# TransmitterSchematic.net
KiCad netlist of a schematic drawn in EAGLE
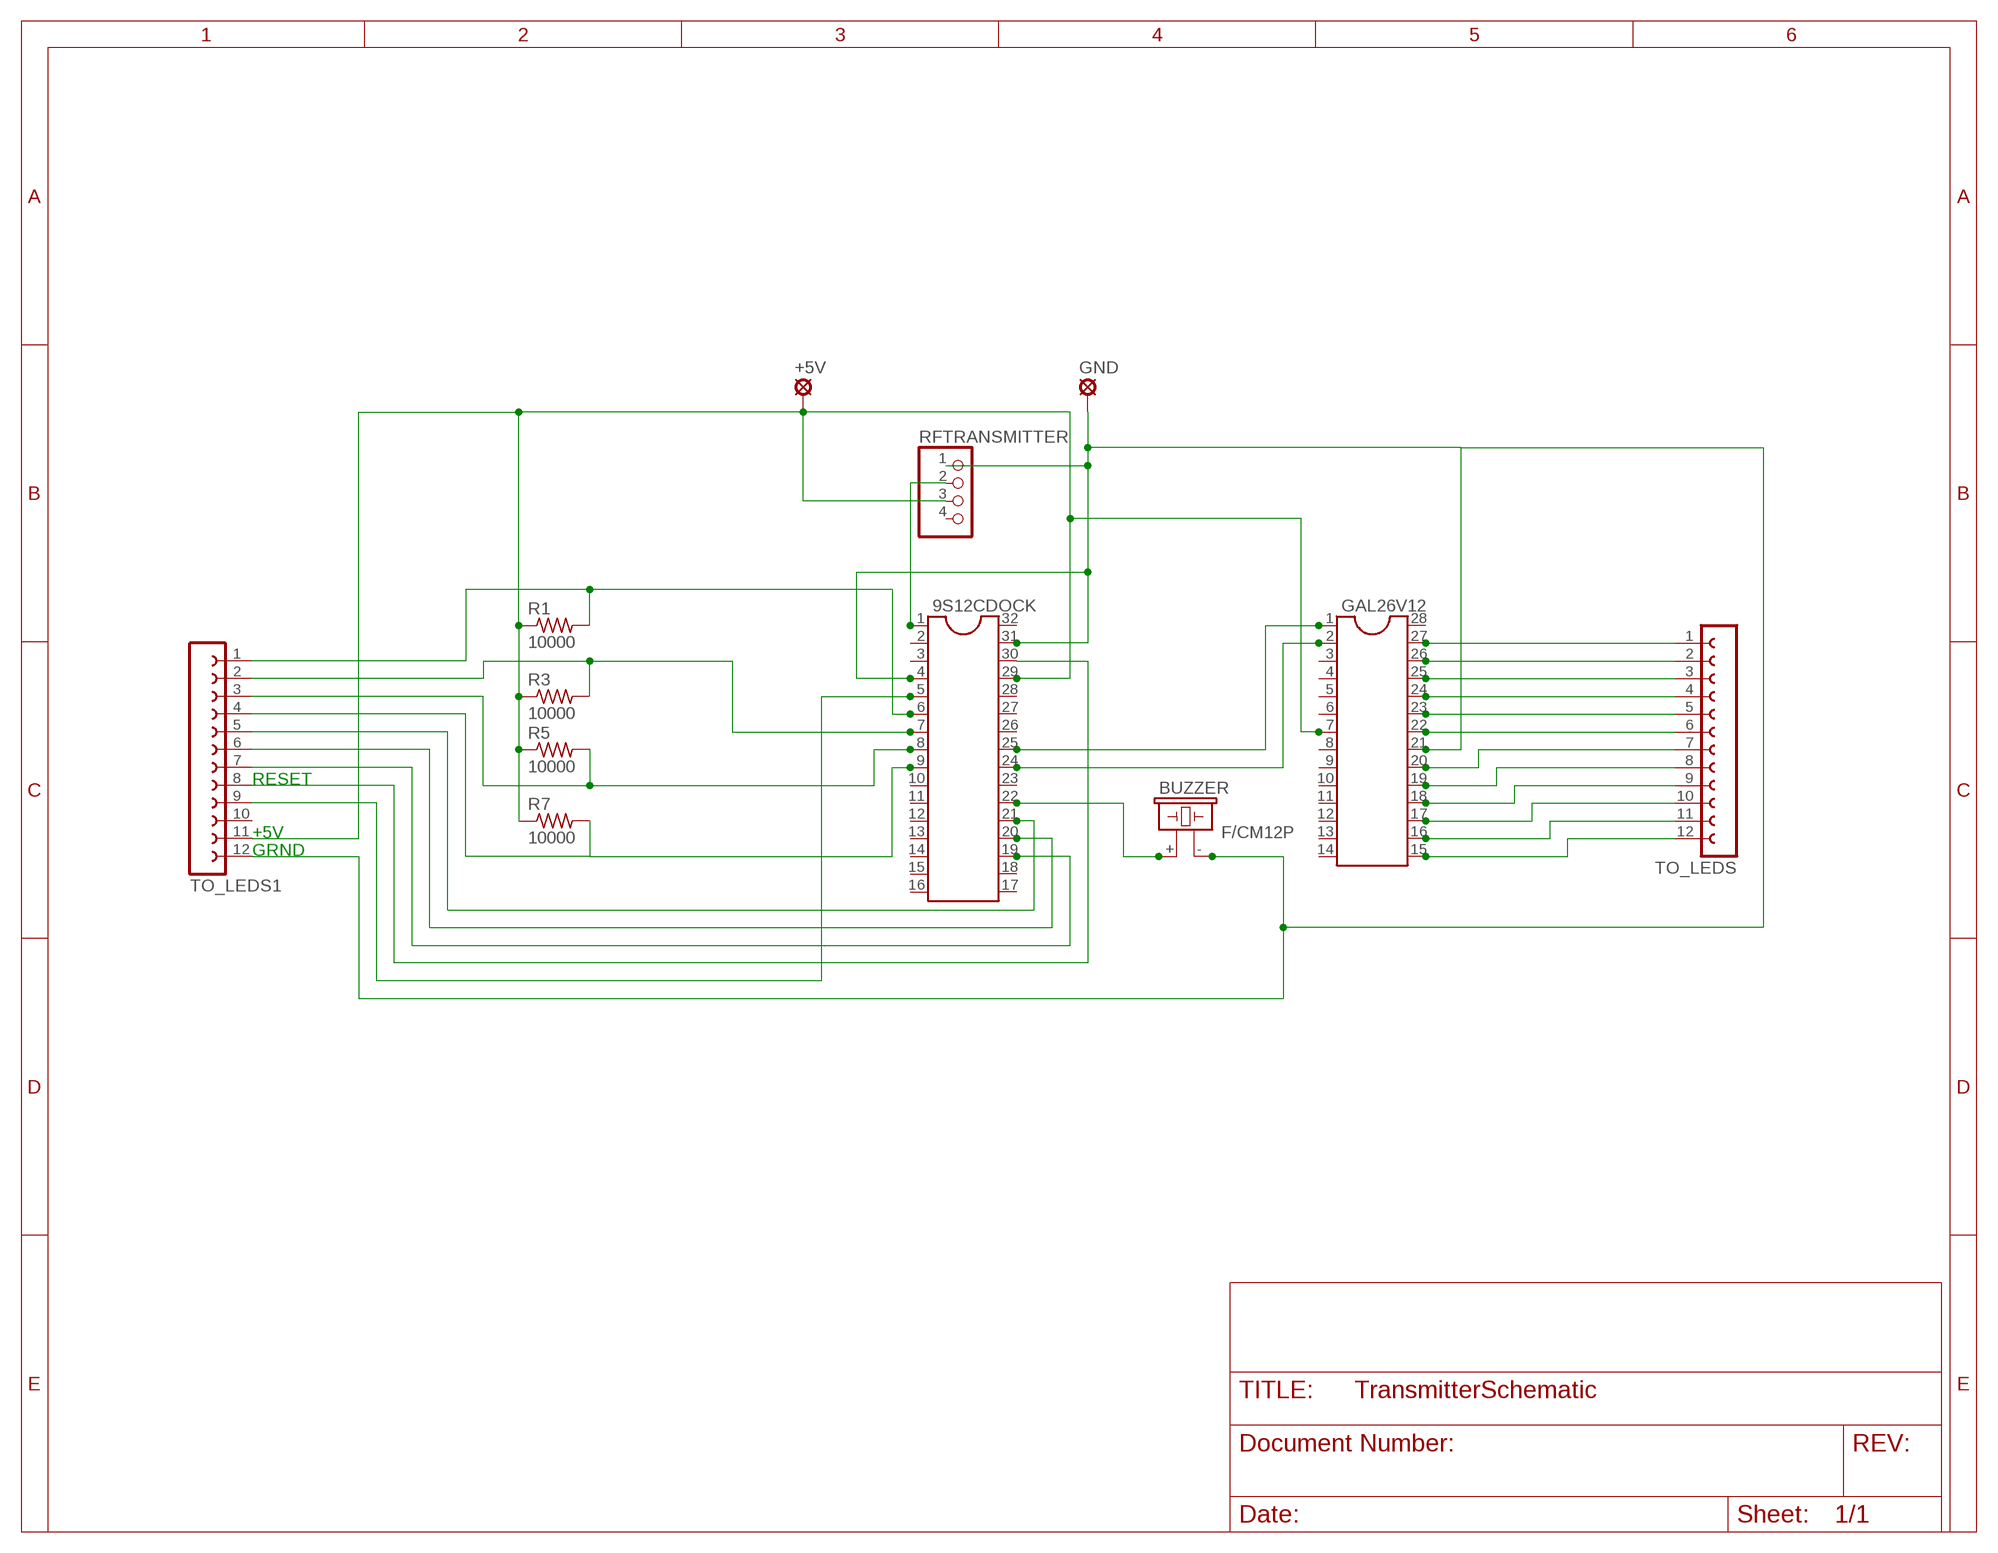
[diagram p0: schematic, sheet 1]

(export (version "E")
  (design (tool "Eeschema 10.0.6"))
  (components
    (comp (ref "+5V")
      (value "LSP10")
      (footprint "eagle-import:LSP10")
      (libsource (lib "eagle-import") (part "LSP10"))
    )
    (comp (ref "9S12CDOCK")
      (value "DIL32")
      (footprint "eagle-import:DIL32")
      (libsource (lib "eagle-import") (part "DIL32"))
    )
    (comp (ref "BUZZER")
      (value "F/CM12P")
      (footprint "eagle-import:F_CM12P")
      (libsource (lib "eagle-import") (part "F/CM12P"))
    )
    (comp (ref "GAL26V12")
      (value "DIL28")
      (footprint "eagle-import:DIL28-6")
      (libsource (lib "eagle-import") (part "DIL28"))
    )
    (comp (ref "GND")
      (value "LSP10")
      (footprint "eagle-import:LSP10")
      (libsource (lib "eagle-import") (part "LSP10"))
    )
    (comp (ref "R1")
      (value "10000")
      (footprint "eagle-import:0204_5")
      (libsource (lib "eagle-import") (part "R-US_0204/5"))
    )
    (comp (ref "R3")
      (value "10000")
      (footprint "eagle-import:0204_5")
      (libsource (lib "eagle-import") (part "R-US_0204/5"))
    )
    (comp (ref "R5")
      (value "10000")
      (footprint "eagle-import:0204_5")
      (libsource (lib "eagle-import") (part "R-US_0204/5"))
    )
    (comp (ref "R7")
      (value "10000")
      (footprint "eagle-import:0204_5")
      (libsource (lib "eagle-import") (part "R-US_0204/5"))
    )
    (comp (ref "RFTRANSMITTER")
      (value "PINHD-1X4")
      (footprint "eagle-import:1X04")
      (libsource (lib "eagle-import") (part "PINHD-1X4"))
    )
    (comp (ref "TO_LEDS")
      (value "FE12-1")
      (footprint "eagle-import:FE12")
      (libsource (lib "eagle-import") (part "FE12-1"))
    )
    (comp (ref "TO_LEDS1")
      (value "FE12-1")
      (footprint "eagle-import:FE12")
      (libsource (lib "eagle-import") (part "FE12-1"))
    )
  )
  (nets
    (net (code "1") (name "Net-(+5V-PadMP)") (class "Default")
      (node (ref "+5V") (pin "MP") (pinfunction "MP_MP") (pintype "passive"))
      (node (ref "9S12CDOCK") (pin "29") (pinfunction "29_29") (pintype "passive"))
      (node (ref "GAL26V12") (pin "7") (pinfunction "7_7") (pintype "passive"))
      (node (ref "R1") (pin "1") (pinfunction "1_1") (pintype "passive"))
      (node (ref "R3") (pin "1") (pinfunction "1_1") (pintype "passive"))
      (node (ref "R5") (pin "1") (pinfunction "1_1") (pintype "passive"))
      (node (ref "R7") (pin "1") (pinfunction "1_1") (pintype "passive"))
      (node (ref "RFTRANSMITTER") (pin "3") (pinfunction "3_3") (pintype "passive"))
      (node (ref "TO_LEDS1") (pin "11") (pinfunction "11_11") (pintype "passive"))
    )
    (net (code "2") (name "Net-(9S12CDOCK-Pad1)") (class "Default")
      (node (ref "9S12CDOCK") (pin "1") (pinfunction "1_1") (pintype "passive"))
      (node (ref "RFTRANSMITTER") (pin "2") (pinfunction "2_2") (pintype "passive"))
    )
    (net (code "3") (name "Net-(9S12CDOCK-Pad5)") (class "Default")
      (node (ref "9S12CDOCK") (pin "5") (pinfunction "5_5") (pintype "passive"))
      (node (ref "TO_LEDS1") (pin "9") (pinfunction "9_9") (pintype "passive"))
    )
    (net (code "4") (name "Net-(9S12CDOCK-Pad6)") (class "Default")
      (node (ref "9S12CDOCK") (pin "6") (pinfunction "6_6") (pintype "passive"))
      (node (ref "R1") (pin "2") (pinfunction "2_2") (pintype "passive"))
      (node (ref "TO_LEDS1") (pin "1") (pinfunction "1_1") (pintype "passive"))
    )
    (net (code "5") (name "Net-(9S12CDOCK-Pad7)") (class "Default")
      (node (ref "9S12CDOCK") (pin "7") (pinfunction "7_7") (pintype "passive"))
      (node (ref "R3") (pin "2") (pinfunction "2_2") (pintype "passive"))
      (node (ref "TO_LEDS1") (pin "2") (pinfunction "2_2") (pintype "passive"))
    )
    (net (code "6") (name "Net-(9S12CDOCK-Pad8)") (class "Default")
      (node (ref "9S12CDOCK") (pin "8") (pinfunction "8_8") (pintype "passive"))
      (node (ref "R5") (pin "2") (pinfunction "2_2") (pintype "passive"))
      (node (ref "TO_LEDS1") (pin "3") (pinfunction "3_3") (pintype "passive"))
    )
    (net (code "7") (name "Net-(9S12CDOCK-Pad9)") (class "Default")
      (node (ref "9S12CDOCK") (pin "9") (pinfunction "9_9") (pintype "passive"))
      (node (ref "R7") (pin "2") (pinfunction "2_2") (pintype "passive"))
      (node (ref "TO_LEDS1") (pin "4") (pinfunction "4_4") (pintype "passive"))
    )
    (net (code "8") (name "Net-(9S12CDOCK-Pad19)") (class "Default")
      (node (ref "9S12CDOCK") (pin "19") (pinfunction "19_19") (pintype "passive"))
      (node (ref "TO_LEDS1") (pin "7") (pinfunction "7_7") (pintype "passive"))
    )
    (net (code "9") (name "Net-(9S12CDOCK-Pad20)") (class "Default")
      (node (ref "9S12CDOCK") (pin "20") (pinfunction "20_20") (pintype "passive"))
      (node (ref "TO_LEDS1") (pin "6") (pinfunction "6_6") (pintype "passive"))
    )
    (net (code "10") (name "Net-(9S12CDOCK-Pad21)") (class "Default")
      (node (ref "9S12CDOCK") (pin "21") (pinfunction "21_21") (pintype "passive"))
      (node (ref "TO_LEDS1") (pin "5") (pinfunction "5_5") (pintype "passive"))
    )
    (net (code "11") (name "Net-(9S12CDOCK-Pad24)") (class "Default")
      (node (ref "9S12CDOCK") (pin "24") (pinfunction "24_24") (pintype "passive"))
      (node (ref "GAL26V12") (pin "2") (pinfunction "2_2") (pintype "passive"))
    )
    (net (code "12") (name "Net-(9S12CDOCK-Pad25)") (class "Default")
      (node (ref "9S12CDOCK") (pin "25") (pinfunction "25_25") (pintype "passive"))
      (node (ref "GAL26V12") (pin "1") (pinfunction "1_1") (pintype "passive"))
    )
    (net (code "13") (name "Net-(9S12CDOCK-Pad30)") (class "Default")
      (node (ref "9S12CDOCK") (pin "30") (pinfunction "30_30") (pintype "passive"))
      (node (ref "TO_LEDS1") (pin "8") (pinfunction "8_8") (pintype "passive"))
    )
    (net (code "14") (name "Net-(BUZZER-1)") (class "Default")
      (node (ref "9S12CDOCK") (pin "22") (pinfunction "22_22") (pintype "passive"))
      (node (ref "BUZZER") (pin "+") (pinfunction "1_+") (pintype "passive"))
    )
    (net (code "15") (name "Net-(BUZZER-2)") (class "Default")
      (node (ref "9S12CDOCK") (pin "31") (pinfunction "31_31") (pintype "passive"))
      (node (ref "9S12CDOCK") (pin "4") (pinfunction "4_4") (pintype "passive"))
      (node (ref "BUZZER") (pin "-") (pinfunction "2_-") (pintype "passive"))
      (node (ref "GAL26V12") (pin "21") (pinfunction "21_21") (pintype "passive"))
      (node (ref "GND") (pin "MP") (pinfunction "MP_MP") (pintype "passive"))
      (node (ref "RFTRANSMITTER") (pin "1") (pinfunction "1_1") (pintype "passive"))
      (node (ref "TO_LEDS1") (pin "12") (pinfunction "12_12") (pintype "passive"))
    )
    (net (code "16") (name "Net-(GAL26V12-Pad15)") (class "Default")
      (node (ref "GAL26V12") (pin "15") (pinfunction "15_15") (pintype "passive"))
      (node (ref "TO_LEDS") (pin "12") (pinfunction "12_12") (pintype "passive"))
    )
    (net (code "17") (name "Net-(GAL26V12-Pad16)") (class "Default")
      (node (ref "GAL26V12") (pin "16") (pinfunction "16_16") (pintype "passive"))
      (node (ref "TO_LEDS") (pin "11") (pinfunction "11_11") (pintype "passive"))
    )
    (net (code "18") (name "Net-(GAL26V12-Pad17)") (class "Default")
      (node (ref "GAL26V12") (pin "17") (pinfunction "17_17") (pintype "passive"))
      (node (ref "TO_LEDS") (pin "10") (pinfunction "10_10") (pintype "passive"))
    )
    (net (code "19") (name "Net-(GAL26V12-Pad18)") (class "Default")
      (node (ref "GAL26V12") (pin "18") (pinfunction "18_18") (pintype "passive"))
      (node (ref "TO_LEDS") (pin "9") (pinfunction "9_9") (pintype "passive"))
    )
    (net (code "20") (name "Net-(GAL26V12-Pad19)") (class "Default")
      (node (ref "GAL26V12") (pin "19") (pinfunction "19_19") (pintype "passive"))
      (node (ref "TO_LEDS") (pin "8") (pinfunction "8_8") (pintype "passive"))
    )
    (net (code "21") (name "Net-(GAL26V12-Pad20)") (class "Default")
      (node (ref "GAL26V12") (pin "20") (pinfunction "20_20") (pintype "passive"))
      (node (ref "TO_LEDS") (pin "7") (pinfunction "7_7") (pintype "passive"))
    )
    (net (code "22") (name "Net-(GAL26V12-Pad22)") (class "Default")
      (node (ref "GAL26V12") (pin "22") (pinfunction "22_22") (pintype "passive"))
      (node (ref "TO_LEDS") (pin "6") (pinfunction "6_6") (pintype "passive"))
    )
    (net (code "23") (name "Net-(GAL26V12-Pad23)") (class "Default")
      (node (ref "GAL26V12") (pin "23") (pinfunction "23_23") (pintype "passive"))
      (node (ref "TO_LEDS") (pin "5") (pinfunction "5_5") (pintype "passive"))
    )
    (net (code "24") (name "Net-(GAL26V12-Pad24)") (class "Default")
      (node (ref "GAL26V12") (pin "24") (pinfunction "24_24") (pintype "passive"))
      (node (ref "TO_LEDS") (pin "4") (pinfunction "4_4") (pintype "passive"))
    )
    (net (code "25") (name "Net-(GAL26V12-Pad25)") (class "Default")
      (node (ref "GAL26V12") (pin "25") (pinfunction "25_25") (pintype "passive"))
      (node (ref "TO_LEDS") (pin "3") (pinfunction "3_3") (pintype "passive"))
    )
    (net (code "26") (name "Net-(GAL26V12-Pad26)") (class "Default")
      (node (ref "GAL26V12") (pin "26") (pinfunction "26_26") (pintype "passive"))
      (node (ref "TO_LEDS") (pin "2") (pinfunction "2_2") (pintype "passive"))
    )
    (net (code "27") (name "Net-(GAL26V12-Pad27)") (class "Default")
      (node (ref "GAL26V12") (pin "27") (pinfunction "27_27") (pintype "passive"))
      (node (ref "TO_LEDS") (pin "1") (pinfunction "1_1") (pintype "passive"))
    )
    (net (code "28") (name "unconnected-(9S12CDOCK-Pad2)") (class "Default")
      (node (ref "9S12CDOCK") (pin "2") (pinfunction "2_2") (pintype "passive"))
    )
    (net (code "29") (name "unconnected-(9S12CDOCK-Pad3)") (class "Default")
      (node (ref "9S12CDOCK") (pin "3") (pinfunction "3_3") (pintype "passive"))
    )
    (net (code "30") (name "unconnected-(9S12CDOCK-Pad10)") (class "Default")
      (node (ref "9S12CDOCK") (pin "10") (pinfunction "10_10") (pintype "passive"))
    )
    (net (code "31") (name "unconnected-(9S12CDOCK-Pad11)") (class "Default")
      (node (ref "9S12CDOCK") (pin "11") (pinfunction "11_11") (pintype "passive"))
    )
    (net (code "32") (name "unconnected-(9S12CDOCK-Pad12)") (class "Default")
      (node (ref "9S12CDOCK") (pin "12") (pinfunction "12_12") (pintype "passive"))
    )
    (net (code "33") (name "unconnected-(9S12CDOCK-Pad13)") (class "Default")
      (node (ref "9S12CDOCK") (pin "13") (pinfunction "13_13") (pintype "passive"))
    )
    (net (code "34") (name "unconnected-(9S12CDOCK-Pad14)") (class "Default")
      (node (ref "9S12CDOCK") (pin "14") (pinfunction "14_14") (pintype "passive"))
    )
    (net (code "35") (name "unconnected-(9S12CDOCK-Pad15)") (class "Default")
      (node (ref "9S12CDOCK") (pin "15") (pinfunction "15_15") (pintype "passive"))
    )
    (net (code "36") (name "unconnected-(9S12CDOCK-Pad16)") (class "Default")
      (node (ref "9S12CDOCK") (pin "16") (pinfunction "16_16") (pintype "passive"))
    )
    (net (code "37") (name "unconnected-(9S12CDOCK-Pad17)") (class "Default")
      (node (ref "9S12CDOCK") (pin "17") (pinfunction "17_17") (pintype "passive"))
    )
    (net (code "38") (name "unconnected-(9S12CDOCK-Pad18)") (class "Default")
      (node (ref "9S12CDOCK") (pin "18") (pinfunction "18_18") (pintype "passive"))
    )
    (net (code "39") (name "unconnected-(9S12CDOCK-Pad23)") (class "Default")
      (node (ref "9S12CDOCK") (pin "23") (pinfunction "23_23") (pintype "passive"))
    )
    (net (code "40") (name "unconnected-(9S12CDOCK-Pad26)") (class "Default")
      (node (ref "9S12CDOCK") (pin "26") (pinfunction "26_26") (pintype "passive"))
    )
    (net (code "41") (name "unconnected-(9S12CDOCK-Pad27)") (class "Default")
      (node (ref "9S12CDOCK") (pin "27") (pinfunction "27_27") (pintype "passive"))
    )
    (net (code "42") (name "unconnected-(9S12CDOCK-Pad28)") (class "Default")
      (node (ref "9S12CDOCK") (pin "28") (pinfunction "28_28") (pintype "passive"))
    )
    (net (code "43") (name "unconnected-(9S12CDOCK-Pad32)") (class "Default")
      (node (ref "9S12CDOCK") (pin "32") (pinfunction "32_32") (pintype "passive"))
    )
    (net (code "44") (name "unconnected-(GAL26V12-Pad3)") (class "Default")
      (node (ref "GAL26V12") (pin "3") (pinfunction "3_3") (pintype "passive"))
    )
    (net (code "45") (name "unconnected-(GAL26V12-Pad4)") (class "Default")
      (node (ref "GAL26V12") (pin "4") (pinfunction "4_4") (pintype "passive"))
    )
    (net (code "46") (name "unconnected-(GAL26V12-Pad5)") (class "Default")
      (node (ref "GAL26V12") (pin "5") (pinfunction "5_5") (pintype "passive"))
    )
    (net (code "47") (name "unconnected-(GAL26V12-Pad6)") (class "Default")
      (node (ref "GAL26V12") (pin "6") (pinfunction "6_6") (pintype "passive"))
    )
    (net (code "48") (name "unconnected-(GAL26V12-Pad8)") (class "Default")
      (node (ref "GAL26V12") (pin "8") (pinfunction "8_8") (pintype "passive"))
    )
    (net (code "49") (name "unconnected-(GAL26V12-Pad9)") (class "Default")
      (node (ref "GAL26V12") (pin "9") (pinfunction "9_9") (pintype "passive"))
    )
    (net (code "50") (name "unconnected-(GAL26V12-Pad10)") (class "Default")
      (node (ref "GAL26V12") (pin "10") (pinfunction "10_10") (pintype "passive"))
    )
    (net (code "51") (name "unconnected-(GAL26V12-Pad11)") (class "Default")
      (node (ref "GAL26V12") (pin "11") (pinfunction "11_11") (pintype "passive"))
    )
    (net (code "52") (name "unconnected-(GAL26V12-Pad12)") (class "Default")
      (node (ref "GAL26V12") (pin "12") (pinfunction "12_12") (pintype "passive"))
    )
    (net (code "53") (name "unconnected-(GAL26V12-Pad13)") (class "Default")
      (node (ref "GAL26V12") (pin "13") (pinfunction "13_13") (pintype "passive"))
    )
    (net (code "54") (name "unconnected-(GAL26V12-Pad14)") (class "Default")
      (node (ref "GAL26V12") (pin "14") (pinfunction "14_14") (pintype "passive"))
    )
    (net (code "55") (name "unconnected-(GAL26V12-Pad28)") (class "Default")
      (node (ref "GAL26V12") (pin "28") (pinfunction "28_28") (pintype "passive"))
    )
    (net (code "56") (name "unconnected-(RFTRANSMITTER-Pad4)") (class "Default")
      (node (ref "RFTRANSMITTER") (pin "4") (pinfunction "4_4") (pintype "passive"))
    )
    (net (code "57") (name "unconnected-(TO_LEDS1-Pad10)") (class "Default")
      (node (ref "TO_LEDS1") (pin "10") (pinfunction "10_10") (pintype "passive"))
    )
  )
)
